# shift_reg.net
KiCad netlist of a schematic drawn in EAGLE
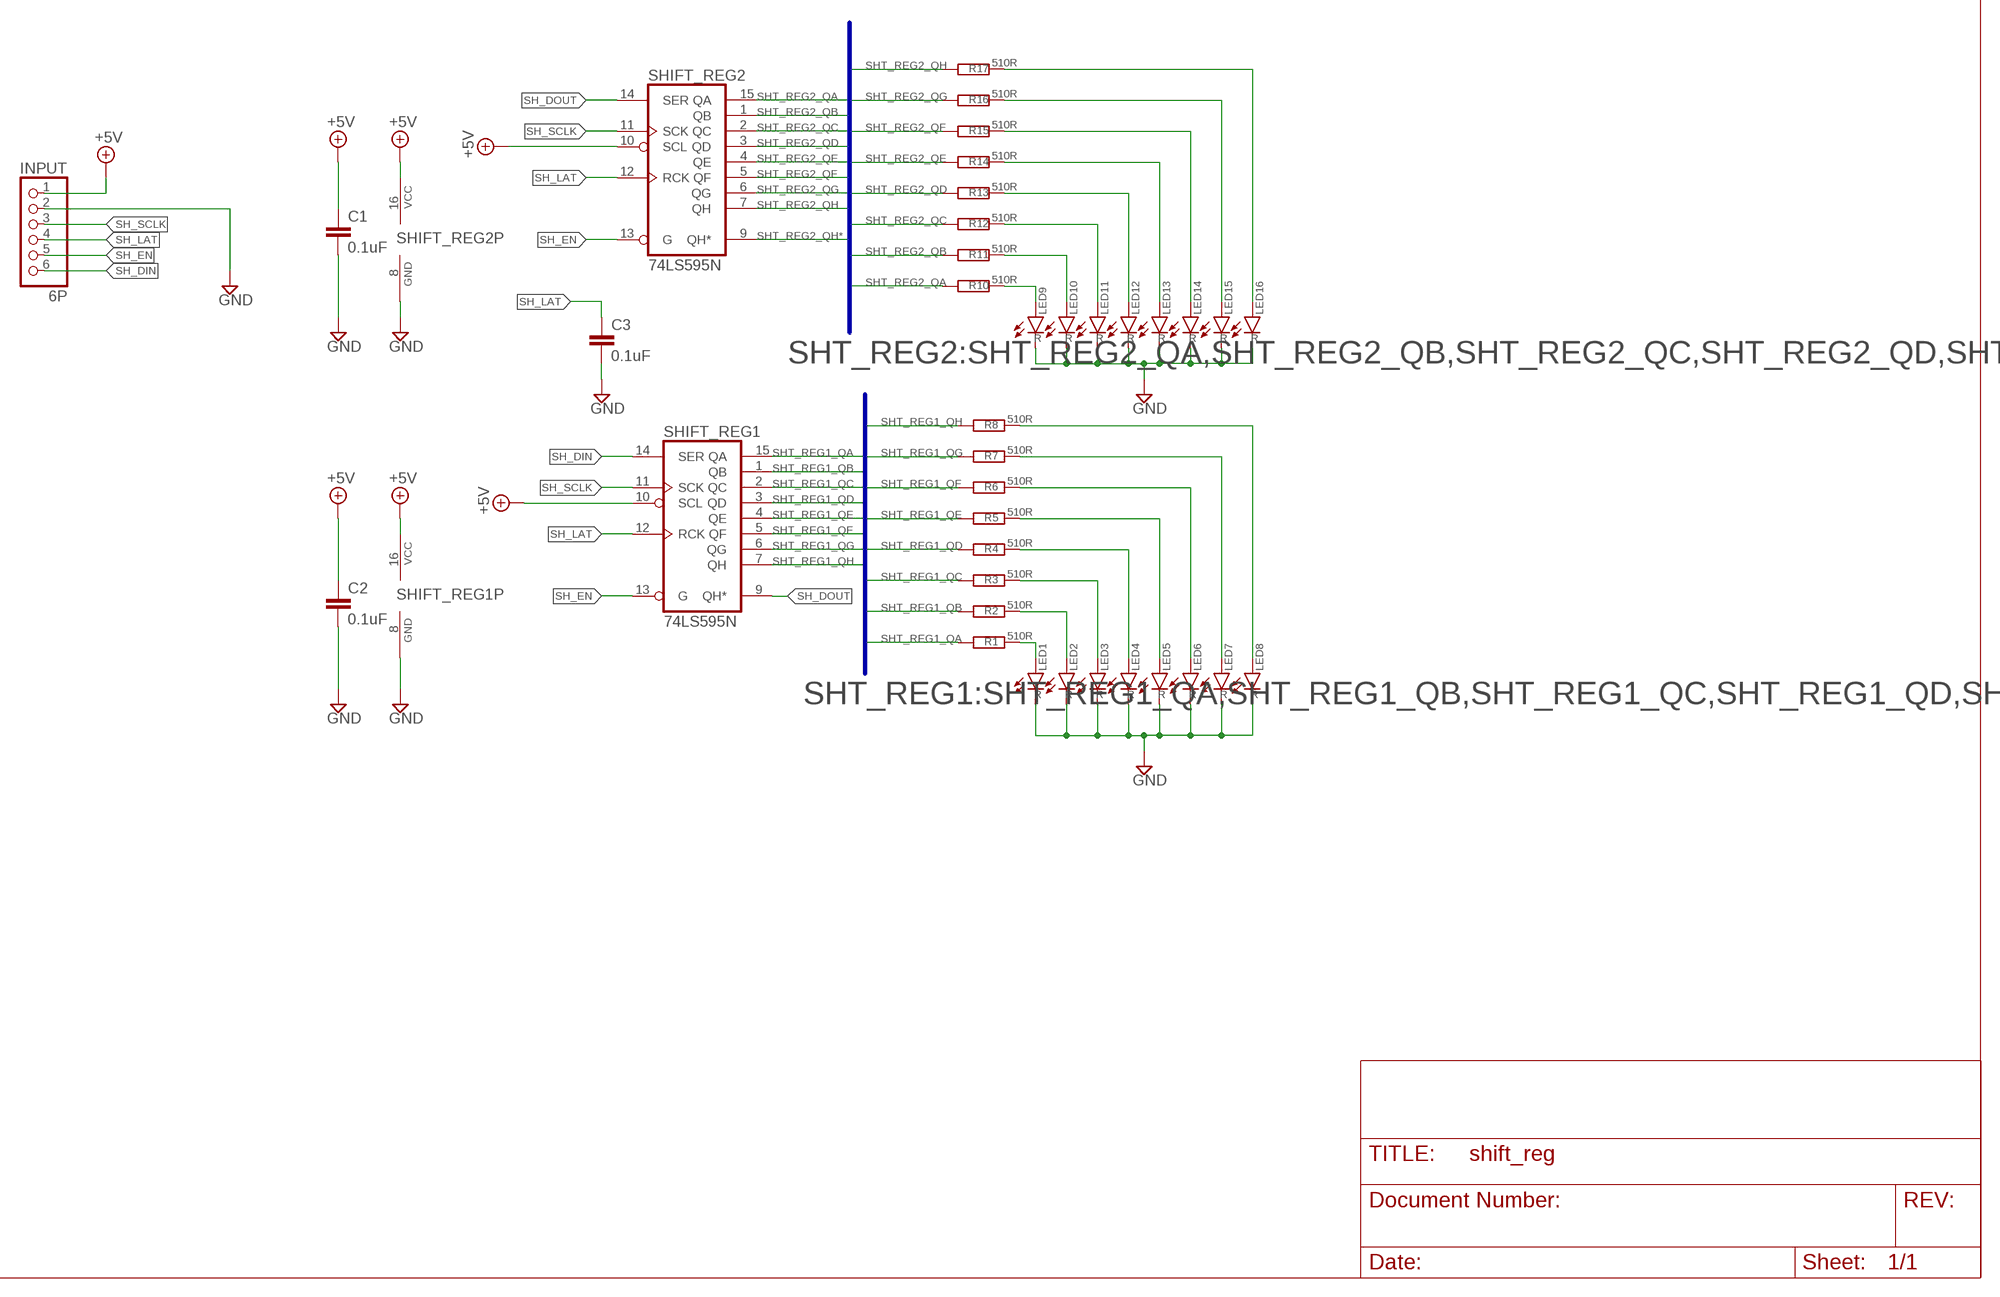
[diagram p0: schematic, sheet 1]

(export (version "E")
  (design (tool "Eeschema 10.0.6"))
  (components
    (comp (ref "C1")
      (value "0.1uF")
      (footprint "eagle-import:C050-030X075")
      (libsource (lib "eagle-import") (part "C-EU050-030X075"))
    )
    (comp (ref "C2")
      (value "0.1uF")
      (footprint "eagle-import:C050-030X075")
      (libsource (lib "eagle-import") (part "C-EU050-030X075"))
    )
    (comp (ref "C3")
      (value "0.1uF")
      (footprint "eagle-import:C050-030X075")
      (libsource (lib "eagle-import") (part "C-EU050-030X075"))
    )
    (comp (ref "INPUT")
      (value "6P")
      (footprint "eagle-import:1X06_90")
      (libsource (lib "eagle-import") (part "PINHD-1X6/90"))
    )
    (comp (ref "LED1")
      (value "R")
      (footprint "eagle-import:LED5MM")
      (libsource (lib "eagle-import") (part "LED5MM"))
    )
    (comp (ref "LED2")
      (value "R")
      (footprint "eagle-import:LED5MM")
      (libsource (lib "eagle-import") (part "LED5MM"))
    )
    (comp (ref "LED3")
      (value "R")
      (footprint "eagle-import:LED5MM")
      (libsource (lib "eagle-import") (part "LED5MM"))
    )
    (comp (ref "LED4")
      (value "R")
      (footprint "eagle-import:LED5MM")
      (libsource (lib "eagle-import") (part "LED5MM"))
    )
    (comp (ref "LED5")
      (value "R")
      (footprint "eagle-import:LED5MM")
      (libsource (lib "eagle-import") (part "LED5MM"))
    )
    (comp (ref "LED6")
      (value "R")
      (footprint "eagle-import:LED5MM")
      (libsource (lib "eagle-import") (part "LED5MM"))
    )
    (comp (ref "LED7")
      (value "R")
      (footprint "eagle-import:LED5MM")
      (libsource (lib "eagle-import") (part "LED5MM"))
    )
    (comp (ref "LED8")
      (value "R")
      (footprint "eagle-import:LED5MM")
      (libsource (lib "eagle-import") (part "LED5MM"))
    )
    (comp (ref "LED9")
      (value "R")
      (footprint "eagle-import:LED5MM")
      (libsource (lib "eagle-import") (part "LED5MM"))
    )
    (comp (ref "LED10")
      (value "R")
      (footprint "eagle-import:LED5MM")
      (libsource (lib "eagle-import") (part "LED5MM"))
    )
    (comp (ref "LED11")
      (value "R")
      (footprint "eagle-import:LED5MM")
      (libsource (lib "eagle-import") (part "LED5MM"))
    )
    (comp (ref "LED12")
      (value "R")
      (footprint "eagle-import:LED5MM")
      (libsource (lib "eagle-import") (part "LED5MM"))
    )
    (comp (ref "LED13")
      (value "R")
      (footprint "eagle-import:LED5MM")
      (libsource (lib "eagle-import") (part "LED5MM"))
    )
    (comp (ref "LED14")
      (value "R")
      (footprint "eagle-import:LED5MM")
      (libsource (lib "eagle-import") (part "LED5MM"))
    )
    (comp (ref "LED15")
      (value "R")
      (footprint "eagle-import:LED5MM")
      (libsource (lib "eagle-import") (part "LED5MM"))
    )
    (comp (ref "LED16")
      (value "R")
      (footprint "eagle-import:LED5MM")
      (libsource (lib "eagle-import") (part "LED5MM"))
    )
    (comp (ref "R1")
      (value "510R")
      (footprint "eagle-import:0207_10")
      (libsource (lib "eagle-import") (part "R-EU_0207/10"))
    )
    (comp (ref "R2")
      (value "510R")
      (footprint "eagle-import:0207_10")
      (libsource (lib "eagle-import") (part "R-EU_0207/10"))
    )
    (comp (ref "R3")
      (value "510R")
      (footprint "eagle-import:0207_10")
      (libsource (lib "eagle-import") (part "R-EU_0207/10"))
    )
    (comp (ref "R4")
      (value "510R")
      (footprint "eagle-import:0207_10")
      (libsource (lib "eagle-import") (part "R-EU_0207/10"))
    )
    (comp (ref "R5")
      (value "510R")
      (footprint "eagle-import:0207_10")
      (libsource (lib "eagle-import") (part "R-EU_0207/10"))
    )
    (comp (ref "R6")
      (value "510R")
      (footprint "eagle-import:0207_10")
      (libsource (lib "eagle-import") (part "R-EU_0207/10"))
    )
    (comp (ref "R7")
      (value "510R")
      (footprint "eagle-import:0207_10")
      (libsource (lib "eagle-import") (part "R-EU_0207/10"))
    )
    (comp (ref "R8")
      (value "510R")
      (footprint "eagle-import:0207_10")
      (libsource (lib "eagle-import") (part "R-EU_0207/10"))
    )
    (comp (ref "R10")
      (value "510R")
      (footprint "eagle-import:0207_10")
      (libsource (lib "eagle-import") (part "R-EU_0207/10"))
    )
    (comp (ref "R11")
      (value "510R")
      (footprint "eagle-import:0207_10")
      (libsource (lib "eagle-import") (part "R-EU_0207/10"))
    )
    (comp (ref "R12")
      (value "510R")
      (footprint "eagle-import:0207_10")
      (libsource (lib "eagle-import") (part "R-EU_0207/10"))
    )
    (comp (ref "R13")
      (value "510R")
      (footprint "eagle-import:0207_10")
      (libsource (lib "eagle-import") (part "R-EU_0207/10"))
    )
    (comp (ref "R14")
      (value "510R")
      (footprint "eagle-import:0207_10")
      (libsource (lib "eagle-import") (part "R-EU_0207/10"))
    )
    (comp (ref "R15")
      (value "510R")
      (footprint "eagle-import:0207_10")
      (libsource (lib "eagle-import") (part "R-EU_0207/10"))
    )
    (comp (ref "R16")
      (value "510R")
      (footprint "eagle-import:0207_10")
      (libsource (lib "eagle-import") (part "R-EU_0207/10"))
    )
    (comp (ref "R17")
      (value "510R")
      (footprint "eagle-import:0207_10")
      (libsource (lib "eagle-import") (part "R-EU_0207/10"))
    )
    (comp (ref "SHIFT_REG1")
      (value "74LS595N")
      (footprint "eagle-import:DIL16")
      (libsource (lib "eagle-import") (part "74595NLS"))
    )
    (comp (ref "SHIFT_REG2")
      (value "74LS595N")
      (footprint "eagle-import:DIL16")
      (libsource (lib "eagle-import") (part "74595NLS"))
    )
  )
  (nets
    (net (code "4") (name "+5V") (class "Default")
      (node (ref "C1") (pin "1") (pinfunction "1_1") (pintype "passive"))
      (node (ref "C2") (pin "1") (pinfunction "1_1") (pintype "passive"))
      (node (ref "INPUT") (pin "1") (pinfunction "1_1") (pintype "passive"))
      (node (ref "SHIFT_REG1") (pin "10") (pinfunction "SCL_10") (pintype "input"))
      (node (ref "SHIFT_REG1") (pin "16") (pinfunction "VCC_16") (pintype "power_in"))
      (node (ref "SHIFT_REG2") (pin "10") (pinfunction "SCL_10") (pintype "input"))
      (node (ref "SHIFT_REG2") (pin "16") (pinfunction "VCC_16") (pintype "power_in"))
    )
    (net (code "5") (name "/SHT_REG1_QA") (class "Default")
      (node (ref "R1") (pin "1") (pinfunction "1_1") (pintype "passive"))
      (node (ref "SHIFT_REG1") (pin "15") (pinfunction "QA_15") (pintype "tri_state"))
    )
    (net (code "6") (name "/SHT_REG1_QB") (class "Default")
      (node (ref "R2") (pin "1") (pinfunction "1_1") (pintype "passive"))
      (node (ref "SHIFT_REG1") (pin "1") (pinfunction "QB_1") (pintype "tri_state"))
    )
    (net (code "7") (name "/SHT_REG1_QC") (class "Default")
      (node (ref "R3") (pin "1") (pinfunction "1_1") (pintype "passive"))
      (node (ref "SHIFT_REG1") (pin "2") (pinfunction "QC_2") (pintype "tri_state"))
    )
    (net (code "8") (name "/SHT_REG1_QD") (class "Default")
      (node (ref "R4") (pin "1") (pinfunction "1_1") (pintype "passive"))
      (node (ref "SHIFT_REG1") (pin "3") (pinfunction "QD_3") (pintype "tri_state"))
    )
    (net (code "9") (name "/SHT_REG1_QE") (class "Default")
      (node (ref "R5") (pin "1") (pinfunction "1_1") (pintype "passive"))
      (node (ref "SHIFT_REG1") (pin "4") (pinfunction "QE_4") (pintype "tri_state"))
    )
    (net (code "10") (name "/SHT_REG1_QF") (class "Default")
      (node (ref "R6") (pin "1") (pinfunction "1_1") (pintype "passive"))
      (node (ref "SHIFT_REG1") (pin "5") (pinfunction "QF_5") (pintype "tri_state"))
    )
    (net (code "11") (name "/SHT_REG1_QG") (class "Default")
      (node (ref "R7") (pin "1") (pinfunction "1_1") (pintype "passive"))
      (node (ref "SHIFT_REG1") (pin "6") (pinfunction "QG_6") (pintype "tri_state"))
    )
    (net (code "12") (name "/SHT_REG1_QH") (class "Default")
      (node (ref "R8") (pin "1") (pinfunction "1_1") (pintype "passive"))
      (node (ref "SHIFT_REG1") (pin "7") (pinfunction "QH_7") (pintype "tri_state"))
    )
    (net (code "13") (name "/SHT_REG2_QA") (class "Default")
      (node (ref "R10") (pin "1") (pinfunction "1_1") (pintype "passive"))
      (node (ref "SHIFT_REG2") (pin "15") (pinfunction "QA_15") (pintype "tri_state"))
    )
    (net (code "14") (name "/SHT_REG2_QB") (class "Default")
      (node (ref "R11") (pin "1") (pinfunction "1_1") (pintype "passive"))
      (node (ref "SHIFT_REG2") (pin "1") (pinfunction "QB_1") (pintype "tri_state"))
    )
    (net (code "15") (name "/SHT_REG2_QC") (class "Default")
      (node (ref "R12") (pin "1") (pinfunction "1_1") (pintype "passive"))
      (node (ref "SHIFT_REG2") (pin "2") (pinfunction "QC_2") (pintype "tri_state"))
    )
    (net (code "16") (name "/SHT_REG2_QD") (class "Default")
      (node (ref "R13") (pin "1") (pinfunction "1_1") (pintype "passive"))
      (node (ref "SHIFT_REG2") (pin "3") (pinfunction "QD_3") (pintype "tri_state"))
    )
    (net (code "17") (name "/SHT_REG2_QE") (class "Default")
      (node (ref "R14") (pin "1") (pinfunction "1_1") (pintype "passive"))
      (node (ref "SHIFT_REG2") (pin "4") (pinfunction "QE_4") (pintype "tri_state"))
    )
    (net (code "18") (name "/SHT_REG2_QF") (class "Default")
      (node (ref "R15") (pin "1") (pinfunction "1_1") (pintype "passive"))
      (node (ref "SHIFT_REG2") (pin "5") (pinfunction "QF_5") (pintype "tri_state"))
    )
    (net (code "19") (name "/SHT_REG2_QG") (class "Default")
      (node (ref "R16") (pin "1") (pinfunction "1_1") (pintype "passive"))
      (node (ref "SHIFT_REG2") (pin "6") (pinfunction "QG_6") (pintype "tri_state"))
    )
    (net (code "20") (name "/SHT_REG2_QH") (class "Default")
      (node (ref "R17") (pin "1") (pinfunction "1_1") (pintype "passive"))
      (node (ref "SHIFT_REG2") (pin "7") (pinfunction "QH_7") (pintype "tri_state"))
    )
    (net (code "21") (name "/SHT_REG2_QH*") (class "Default")
      (node (ref "SHIFT_REG2") (pin "9") (pinfunction "QH*_9") (pintype "tri_state"))
    )
    (net (code "24") (name "GND") (class "Default")
      (node (ref "C1") (pin "2") (pinfunction "2_2") (pintype "passive"))
      (node (ref "C2") (pin "2") (pinfunction "2_2") (pintype "passive"))
      (node (ref "C3") (pin "2") (pinfunction "2_2") (pintype "passive"))
      (node (ref "INPUT") (pin "2") (pinfunction "2_2") (pintype "passive"))
      (node (ref "LED1") (pin "K") (pinfunction "C_K") (pintype "passive"))
      (node (ref "LED10") (pin "K") (pinfunction "C_K") (pintype "passive"))
      (node (ref "LED11") (pin "K") (pinfunction "C_K") (pintype "passive"))
      (node (ref "LED12") (pin "K") (pinfunction "C_K") (pintype "passive"))
      (node (ref "LED13") (pin "K") (pinfunction "C_K") (pintype "passive"))
      (node (ref "LED14") (pin "K") (pinfunction "C_K") (pintype "passive"))
      (node (ref "LED15") (pin "K") (pinfunction "C_K") (pintype "passive"))
      (node (ref "LED16") (pin "K") (pinfunction "C_K") (pintype "passive"))
      (node (ref "LED2") (pin "K") (pinfunction "C_K") (pintype "passive"))
      (node (ref "LED3") (pin "K") (pinfunction "C_K") (pintype "passive"))
      (node (ref "LED4") (pin "K") (pinfunction "C_K") (pintype "passive"))
      (node (ref "LED5") (pin "K") (pinfunction "C_K") (pintype "passive"))
      (node (ref "LED6") (pin "K") (pinfunction "C_K") (pintype "passive"))
      (node (ref "LED7") (pin "K") (pinfunction "C_K") (pintype "passive"))
      (node (ref "LED8") (pin "K") (pinfunction "C_K") (pintype "passive"))
      (node (ref "LED9") (pin "K") (pinfunction "C_K") (pintype "passive"))
      (node (ref "SHIFT_REG1") (pin "8") (pinfunction "GND_8") (pintype "power_in"))
      (node (ref "SHIFT_REG2") (pin "8") (pinfunction "GND_8") (pintype "power_in"))
    )
    (net (code "25") (name "Net-(LED1-PadA)") (class "Default")
      (node (ref "LED1") (pin "A") (pinfunction "A_A") (pintype "passive"))
      (node (ref "R1") (pin "2") (pinfunction "2_2") (pintype "passive"))
    )
    (net (code "26") (name "Net-(LED2-PadA)") (class "Default")
      (node (ref "LED2") (pin "A") (pinfunction "A_A") (pintype "passive"))
      (node (ref "R2") (pin "2") (pinfunction "2_2") (pintype "passive"))
    )
    (net (code "27") (name "Net-(LED3-PadA)") (class "Default")
      (node (ref "LED3") (pin "A") (pinfunction "A_A") (pintype "passive"))
      (node (ref "R3") (pin "2") (pinfunction "2_2") (pintype "passive"))
    )
    (net (code "28") (name "Net-(LED4-PadA)") (class "Default")
      (node (ref "LED4") (pin "A") (pinfunction "A_A") (pintype "passive"))
      (node (ref "R4") (pin "2") (pinfunction "2_2") (pintype "passive"))
    )
    (net (code "29") (name "Net-(LED5-PadA)") (class "Default")
      (node (ref "LED5") (pin "A") (pinfunction "A_A") (pintype "passive"))
      (node (ref "R5") (pin "2") (pinfunction "2_2") (pintype "passive"))
    )
    (net (code "30") (name "Net-(LED6-PadA)") (class "Default")
      (node (ref "LED6") (pin "A") (pinfunction "A_A") (pintype "passive"))
      (node (ref "R6") (pin "2") (pinfunction "2_2") (pintype "passive"))
    )
    (net (code "31") (name "Net-(LED7-PadA)") (class "Default")
      (node (ref "LED7") (pin "A") (pinfunction "A_A") (pintype "passive"))
      (node (ref "R7") (pin "2") (pinfunction "2_2") (pintype "passive"))
    )
    (net (code "32") (name "Net-(LED8-PadA)") (class "Default")
      (node (ref "LED8") (pin "A") (pinfunction "A_A") (pintype "passive"))
      (node (ref "R8") (pin "2") (pinfunction "2_2") (pintype "passive"))
    )
    (net (code "33") (name "Net-(LED9-PadA)") (class "Default")
      (node (ref "LED9") (pin "A") (pinfunction "A_A") (pintype "passive"))
      (node (ref "R10") (pin "2") (pinfunction "2_2") (pintype "passive"))
    )
    (net (code "34") (name "Net-(LED10-PadA)") (class "Default")
      (node (ref "LED10") (pin "A") (pinfunction "A_A") (pintype "passive"))
      (node (ref "R11") (pin "2") (pinfunction "2_2") (pintype "passive"))
    )
    (net (code "35") (name "Net-(LED11-PadA)") (class "Default")
      (node (ref "LED11") (pin "A") (pinfunction "A_A") (pintype "passive"))
      (node (ref "R12") (pin "2") (pinfunction "2_2") (pintype "passive"))
    )
    (net (code "36") (name "Net-(LED12-PadA)") (class "Default")
      (node (ref "LED12") (pin "A") (pinfunction "A_A") (pintype "passive"))
      (node (ref "R13") (pin "2") (pinfunction "2_2") (pintype "passive"))
    )
    (net (code "37") (name "Net-(LED13-PadA)") (class "Default")
      (node (ref "LED13") (pin "A") (pinfunction "A_A") (pintype "passive"))
      (node (ref "R14") (pin "2") (pinfunction "2_2") (pintype "passive"))
    )
    (net (code "38") (name "Net-(LED14-PadA)") (class "Default")
      (node (ref "LED14") (pin "A") (pinfunction "A_A") (pintype "passive"))
      (node (ref "R15") (pin "2") (pinfunction "2_2") (pintype "passive"))
    )
    (net (code "39") (name "Net-(LED15-PadA)") (class "Default")
      (node (ref "LED15") (pin "A") (pinfunction "A_A") (pintype "passive"))
      (node (ref "R16") (pin "2") (pinfunction "2_2") (pintype "passive"))
    )
    (net (code "40") (name "Net-(LED16-PadA)") (class "Default")
      (node (ref "LED16") (pin "A") (pinfunction "A_A") (pintype "passive"))
      (node (ref "R17") (pin "2") (pinfunction "2_2") (pintype "passive"))
    )
    (net (code "41") (name "SH_DIN") (class "Default")
      (node (ref "INPUT") (pin "6") (pinfunction "6_6") (pintype "passive"))
      (node (ref "SHIFT_REG1") (pin "14") (pinfunction "SER_14") (pintype "input"))
    )
    (net (code "42") (name "SH_DOUT") (class "Default")
      (node (ref "SHIFT_REG1") (pin "9") (pinfunction "QH*_9") (pintype "tri_state"))
      (node (ref "SHIFT_REG2") (pin "14") (pinfunction "SER_14") (pintype "input"))
    )
    (net (code "43") (name "SH_EN") (class "Default")
      (node (ref "INPUT") (pin "5") (pinfunction "5_5") (pintype "passive"))
      (node (ref "SHIFT_REG1") (pin "13") (pinfunction "G_13") (pintype "input"))
      (node (ref "SHIFT_REG2") (pin "13") (pinfunction "G_13") (pintype "input"))
    )
    (net (code "44") (name "SH_LAT") (class "Default")
      (node (ref "C3") (pin "1") (pinfunction "1_1") (pintype "passive"))
      (node (ref "INPUT") (pin "4") (pinfunction "4_4") (pintype "passive"))
      (node (ref "SHIFT_REG1") (pin "12") (pinfunction "RCK_12") (pintype "input"))
      (node (ref "SHIFT_REG2") (pin "12") (pinfunction "RCK_12") (pintype "input"))
    )
    (net (code "45") (name "SH_SCLK") (class "Default")
      (node (ref "INPUT") (pin "3") (pinfunction "3_3") (pintype "passive"))
      (node (ref "SHIFT_REG1") (pin "11") (pinfunction "SCK_11") (pintype "input"))
      (node (ref "SHIFT_REG2") (pin "11") (pinfunction "SCK_11") (pintype "input"))
    )
  )
)
